# RD02.net
KiCad netlist of a schematic drawn in EAGLE
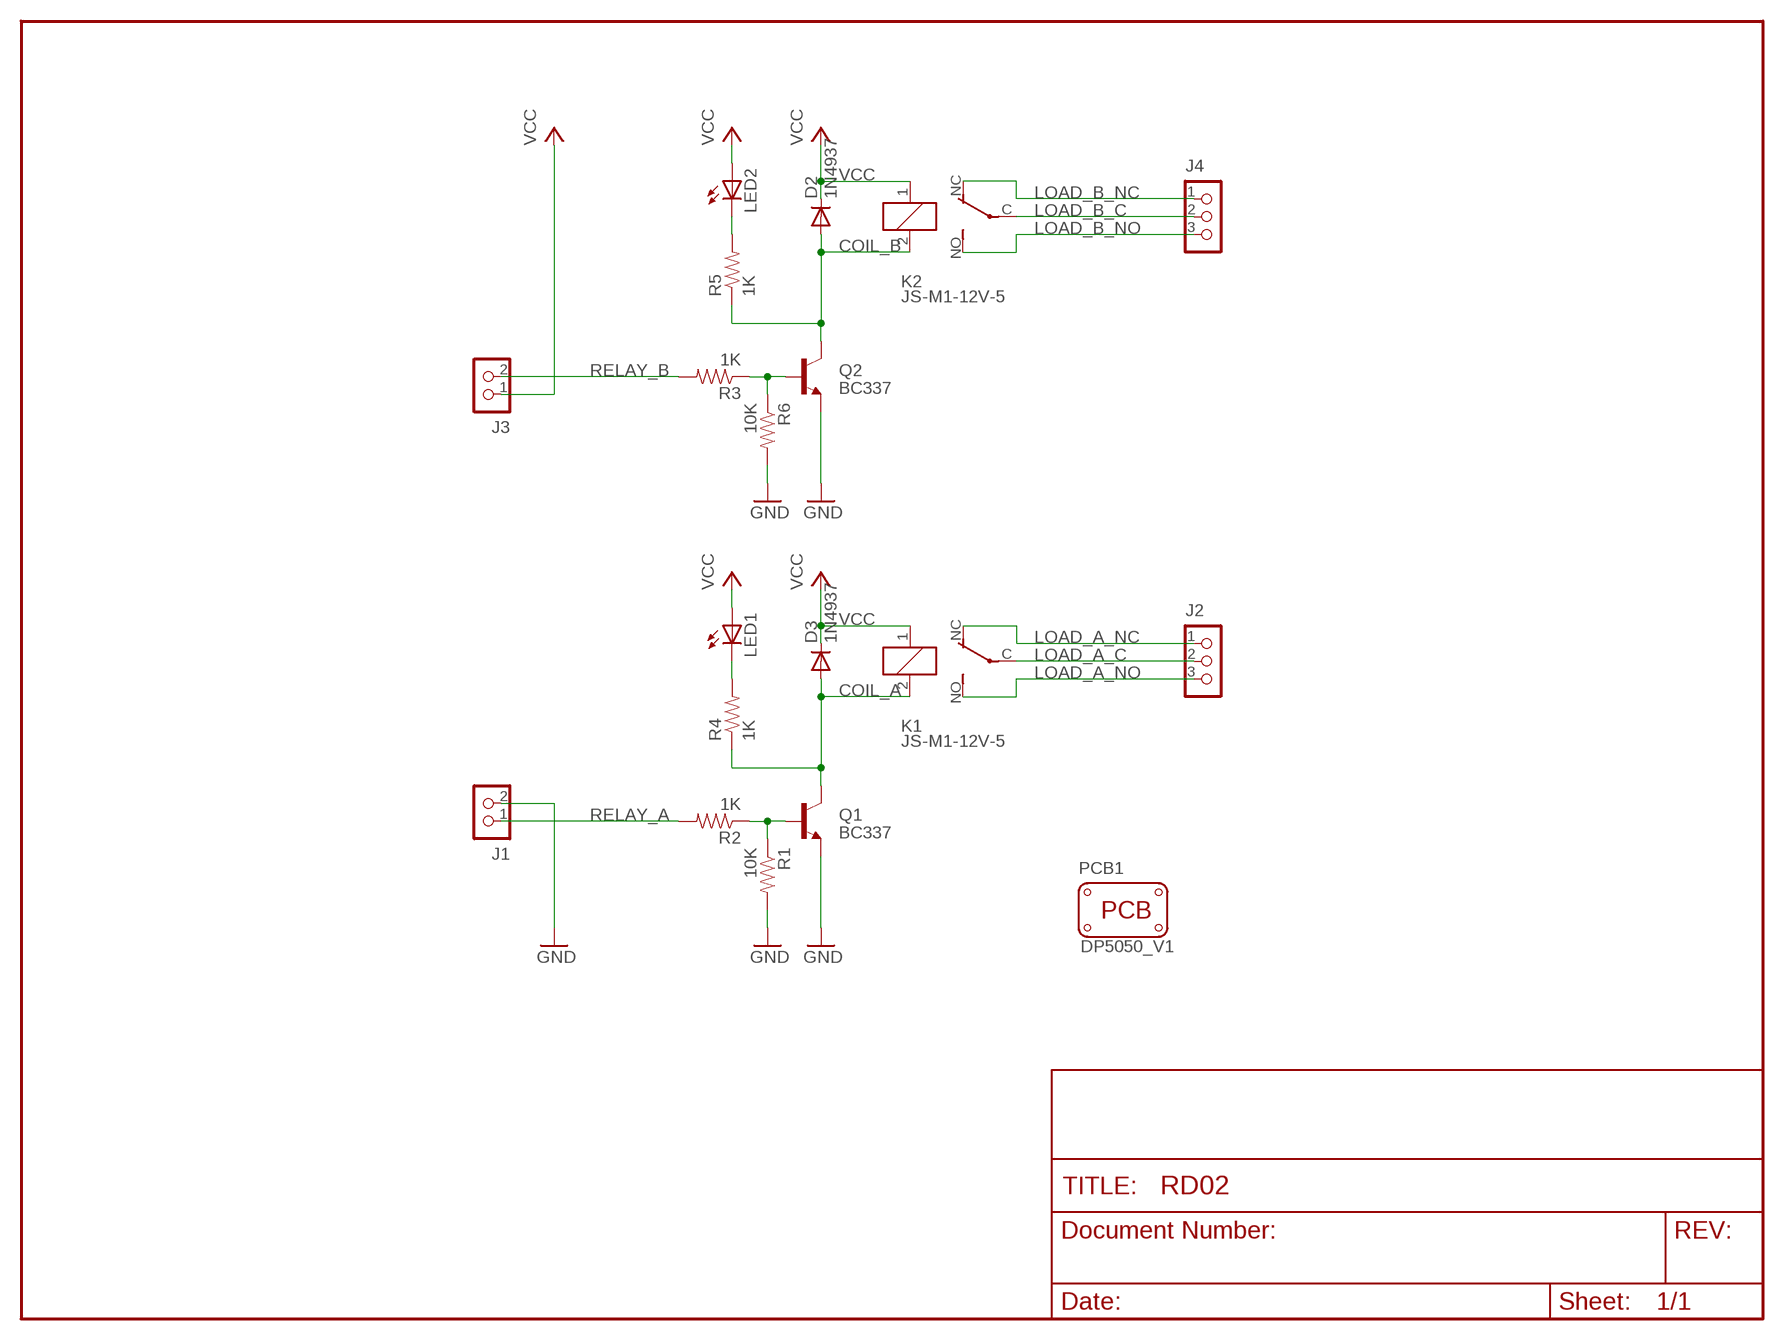
[diagram p0: schematic, sheet 1]

(export (version "E")
  (design (tool "Eeschema 10.0.6"))
  (components
    (comp (ref "D2")
      (value "1N4937")
      (footprint "eagle-import:DO41-10")
      (libsource (lib "eagle-import") (part "1N4933"))
    )
    (comp (ref "D3")
      (value "1N4937")
      (footprint "eagle-import:DO41-10")
      (libsource (lib "eagle-import") (part "1N4933"))
    )
    (comp (ref "J1")
      (value "CON_TERMINAL_BLOCK_02-5MM")
      (footprint "eagle-import:TERMINAL_BLOCK_2P_5")
      (libsource (lib "eagle-import") (part "CON_TERMINAL_BLOCK_02-5MM"))
    )
    (comp (ref "J2")
      (value "CON_TERMINAL_BLOCK_03-5MM")
      (footprint "eagle-import:TERMINAL_BLOCK_3P_5")
      (libsource (lib "eagle-import") (part "CON_TERMINAL_BLOCK_03-5MM"))
    )
    (comp (ref "J3")
      (value "CON_TERMINAL_BLOCK_02-5MM")
      (footprint "eagle-import:TERMINAL_BLOCK_2P_5")
      (libsource (lib "eagle-import") (part "CON_TERMINAL_BLOCK_02-5MM"))
    )
    (comp (ref "J4")
      (value "CON_TERMINAL_BLOCK_03-5MM")
      (footprint "eagle-import:TERMINAL_BLOCK_3P_5")
      (libsource (lib "eagle-import") (part "CON_TERMINAL_BLOCK_03-5MM"))
    )
    (comp (ref "K1")
      (value "JS-M1-12V-5")
      (footprint "eagle-import:JS-M")
      (fields
        (field (name "MF") "FARNELL")
        (field (name "MPN") "JSM1-12V-5")
        (field (name "MF_1") "FARNELL")
        (field (name "MPN_1") "JSM1-12V-5")
        (field (name "OC_FARNELL") "910351")
        (field (name "OC_NEWARK") "14J1764")
      )
      (libsource (lib "eagle-import") (part "JS-M1-12V-5"))
    )
    (comp (ref "K2")
      (value "JS-M1-12V-5")
      (footprint "eagle-import:JS-M")
      (fields
        (field (name "MF") "FARNELL")
        (field (name "MPN") "JSM1-12V-5")
        (field (name "MF_1") "FARNELL")
        (field (name "MPN_1") "JSM1-12V-5")
        (field (name "OC_FARNELL") "910351")
        (field (name "OC_NEWARK") "14J1764")
      )
      (libsource (lib "eagle-import") (part "JS-M1-12V-5"))
    )
    (comp (ref "LED1")
      (value "LED-3MM")
      (footprint "eagle-import:LED-3MM")
      (libsource (lib "eagle-import") (part "LED-3MM"))
    )
    (comp (ref "LED2")
      (value "LED-3MM")
      (footprint "eagle-import:LED-3MM")
      (libsource (lib "eagle-import") (part "LED-3MM"))
    )
    (comp (ref "PCB1")
      (value "PCB_DP_SQUARE-5X5")
      (footprint "eagle-import:DP5050_V1")
      (libsource (lib "eagle-import") (part "PCB_DP_SQUARE-5X5"))
    )
    (comp (ref "Q1")
      (value "BC337")
      (footprint "eagle-import:TO92")
      (libsource (lib "eagle-import") (part "BC337"))
    )
    (comp (ref "Q2")
      (value "BC337")
      (footprint "eagle-import:TO92")
      (libsource (lib "eagle-import") (part "BC337"))
    )
    (comp (ref "R1")
      (value "10K")
      (footprint "eagle-import:AXIAL-0.3")
      (libsource (lib "eagle-import") (part "RESISTORAXIAL-0.3"))
    )
    (comp (ref "R2")
      (value "1K")
      (footprint "eagle-import:AXIAL-0.3")
      (libsource (lib "eagle-import") (part "RESISTORAXIAL-0.3"))
    )
    (comp (ref "R3")
      (value "1K")
      (footprint "eagle-import:AXIAL-0.3")
      (libsource (lib "eagle-import") (part "RESISTORAXIAL-0.3"))
    )
    (comp (ref "R4")
      (value "1K")
      (footprint "eagle-import:AXIAL-0.3")
      (libsource (lib "eagle-import") (part "RESISTORAXIAL-0.3"))
    )
    (comp (ref "R5")
      (value "1K")
      (footprint "eagle-import:AXIAL-0.3")
      (libsource (lib "eagle-import") (part "RESISTORAXIAL-0.3"))
    )
    (comp (ref "R6")
      (value "10K")
      (footprint "eagle-import:AXIAL-0.3")
      (libsource (lib "eagle-import") (part "RESISTORAXIAL-0.3"))
    )
  )
  (nets
    (net (code "1") (name "/COIL_A") (class "Default")
      (node (ref "D3") (pin "A") (pinfunction "A_A") (pintype "passive"))
      (node (ref "K1") (pin "2") (pinfunction "2_2") (pintype "passive"))
      (node (ref "Q1") (pin "3") (pinfunction "C_3") (pintype "passive"))
      (node (ref "R4") (pin "P$1") (pinfunction "1_P$1") (pintype "passive"))
    )
    (net (code "2") (name "/COIL_B") (class "Default")
      (node (ref "D2") (pin "A") (pinfunction "A_A") (pintype "passive"))
      (node (ref "K2") (pin "2") (pinfunction "2_2") (pintype "passive"))
      (node (ref "Q2") (pin "3") (pinfunction "C_3") (pintype "passive"))
      (node (ref "R5") (pin "P$1") (pinfunction "1_P$1") (pintype "passive"))
    )
    (net (code "3") (name "/LOAD_A_C") (class "Default")
      (node (ref "J2") (pin "2") (pinfunction "2_2") (pintype "bidirectional"))
      (node (ref "K1") (pin "C") (pinfunction "P_C") (pintype "passive"))
    )
    (net (code "4") (name "/LOAD_A_NC") (class "Default")
      (node (ref "J2") (pin "1") (pinfunction "1_1") (pintype "bidirectional"))
      (node (ref "K1") (pin "NC") (pinfunction "O_NC") (pintype "passive"))
    )
    (net (code "5") (name "/LOAD_A_NO") (class "Default")
      (node (ref "J2") (pin "3") (pinfunction "3_3") (pintype "bidirectional"))
      (node (ref "K1") (pin "NO") (pinfunction "S_NO") (pintype "passive"))
    )
    (net (code "6") (name "/LOAD_B_C") (class "Default")
      (node (ref "J4") (pin "2") (pinfunction "2_2") (pintype "bidirectional"))
      (node (ref "K2") (pin "C") (pinfunction "P_C") (pintype "passive"))
    )
    (net (code "7") (name "/LOAD_B_NC") (class "Default")
      (node (ref "J4") (pin "1") (pinfunction "1_1") (pintype "bidirectional"))
      (node (ref "K2") (pin "NC") (pinfunction "O_NC") (pintype "passive"))
    )
    (net (code "8") (name "/LOAD_B_NO") (class "Default")
      (node (ref "J4") (pin "3") (pinfunction "3_3") (pintype "bidirectional"))
      (node (ref "K2") (pin "NO") (pinfunction "S_NO") (pintype "passive"))
    )
    (net (code "9") (name "/RELAY_A") (class "Default")
      (node (ref "J1") (pin "1") (pinfunction "1_1") (pintype "passive"))
      (node (ref "R2") (pin "P$2") (pinfunction "2_P$2") (pintype "passive"))
    )
    (net (code "10") (name "/RELAY_B") (class "Default")
      (node (ref "J3") (pin "2") (pinfunction "2_2") (pintype "passive"))
      (node (ref "R3") (pin "P$2") (pinfunction "2_P$2") (pintype "passive"))
    )
    (net (code "11") (name "GND") (class "Default")
      (node (ref "J1") (pin "2") (pinfunction "2_2") (pintype "passive"))
      (node (ref "Q1") (pin "1") (pinfunction "E_1") (pintype "passive"))
      (node (ref "Q2") (pin "1") (pinfunction "E_1") (pintype "passive"))
      (node (ref "R1") (pin "P$2") (pinfunction "2_P$2") (pintype "passive"))
      (node (ref "R6") (pin "P$2") (pinfunction "2_P$2") (pintype "passive"))
    )
    (net (code "12") (name "Net-(LED1-C)") (class "Default")
      (node (ref "LED1") (pin "K") (pinfunction "C_K") (pintype "passive"))
      (node (ref "R4") (pin "P$2") (pinfunction "2_P$2") (pintype "passive"))
    )
    (net (code "13") (name "Net-(LED2-C)") (class "Default")
      (node (ref "LED2") (pin "K") (pinfunction "C_K") (pintype "passive"))
      (node (ref "R5") (pin "P$2") (pinfunction "2_P$2") (pintype "passive"))
    )
    (net (code "14") (name "Net-(Q1-B)") (class "Default")
      (node (ref "Q1") (pin "2") (pinfunction "B_2") (pintype "passive"))
      (node (ref "R1") (pin "P$1") (pinfunction "1_P$1") (pintype "passive"))
      (node (ref "R2") (pin "P$1") (pinfunction "1_P$1") (pintype "passive"))
    )
    (net (code "15") (name "Net-(Q2-B)") (class "Default")
      (node (ref "Q2") (pin "2") (pinfunction "B_2") (pintype "passive"))
      (node (ref "R3") (pin "P$1") (pinfunction "1_P$1") (pintype "passive"))
      (node (ref "R6") (pin "P$1") (pinfunction "1_P$1") (pintype "passive"))
    )
    (net (code "16") (name "VCC") (class "Default")
      (node (ref "D2") (pin "C") (pinfunction "C_C") (pintype "passive"))
      (node (ref "D3") (pin "C") (pinfunction "C_C") (pintype "passive"))
      (node (ref "J3") (pin "1") (pinfunction "1_1") (pintype "passive"))
      (node (ref "K1") (pin "1") (pinfunction "1_1") (pintype "passive"))
      (node (ref "K2") (pin "1") (pinfunction "1_1") (pintype "passive"))
      (node (ref "LED1") (pin "A") (pinfunction "A_A") (pintype "passive"))
      (node (ref "LED2") (pin "A") (pinfunction "A_A") (pintype "passive"))
    )
  )
)
